# rf-transmitter.net
KiCad netlist of a schematic drawn in EAGLE
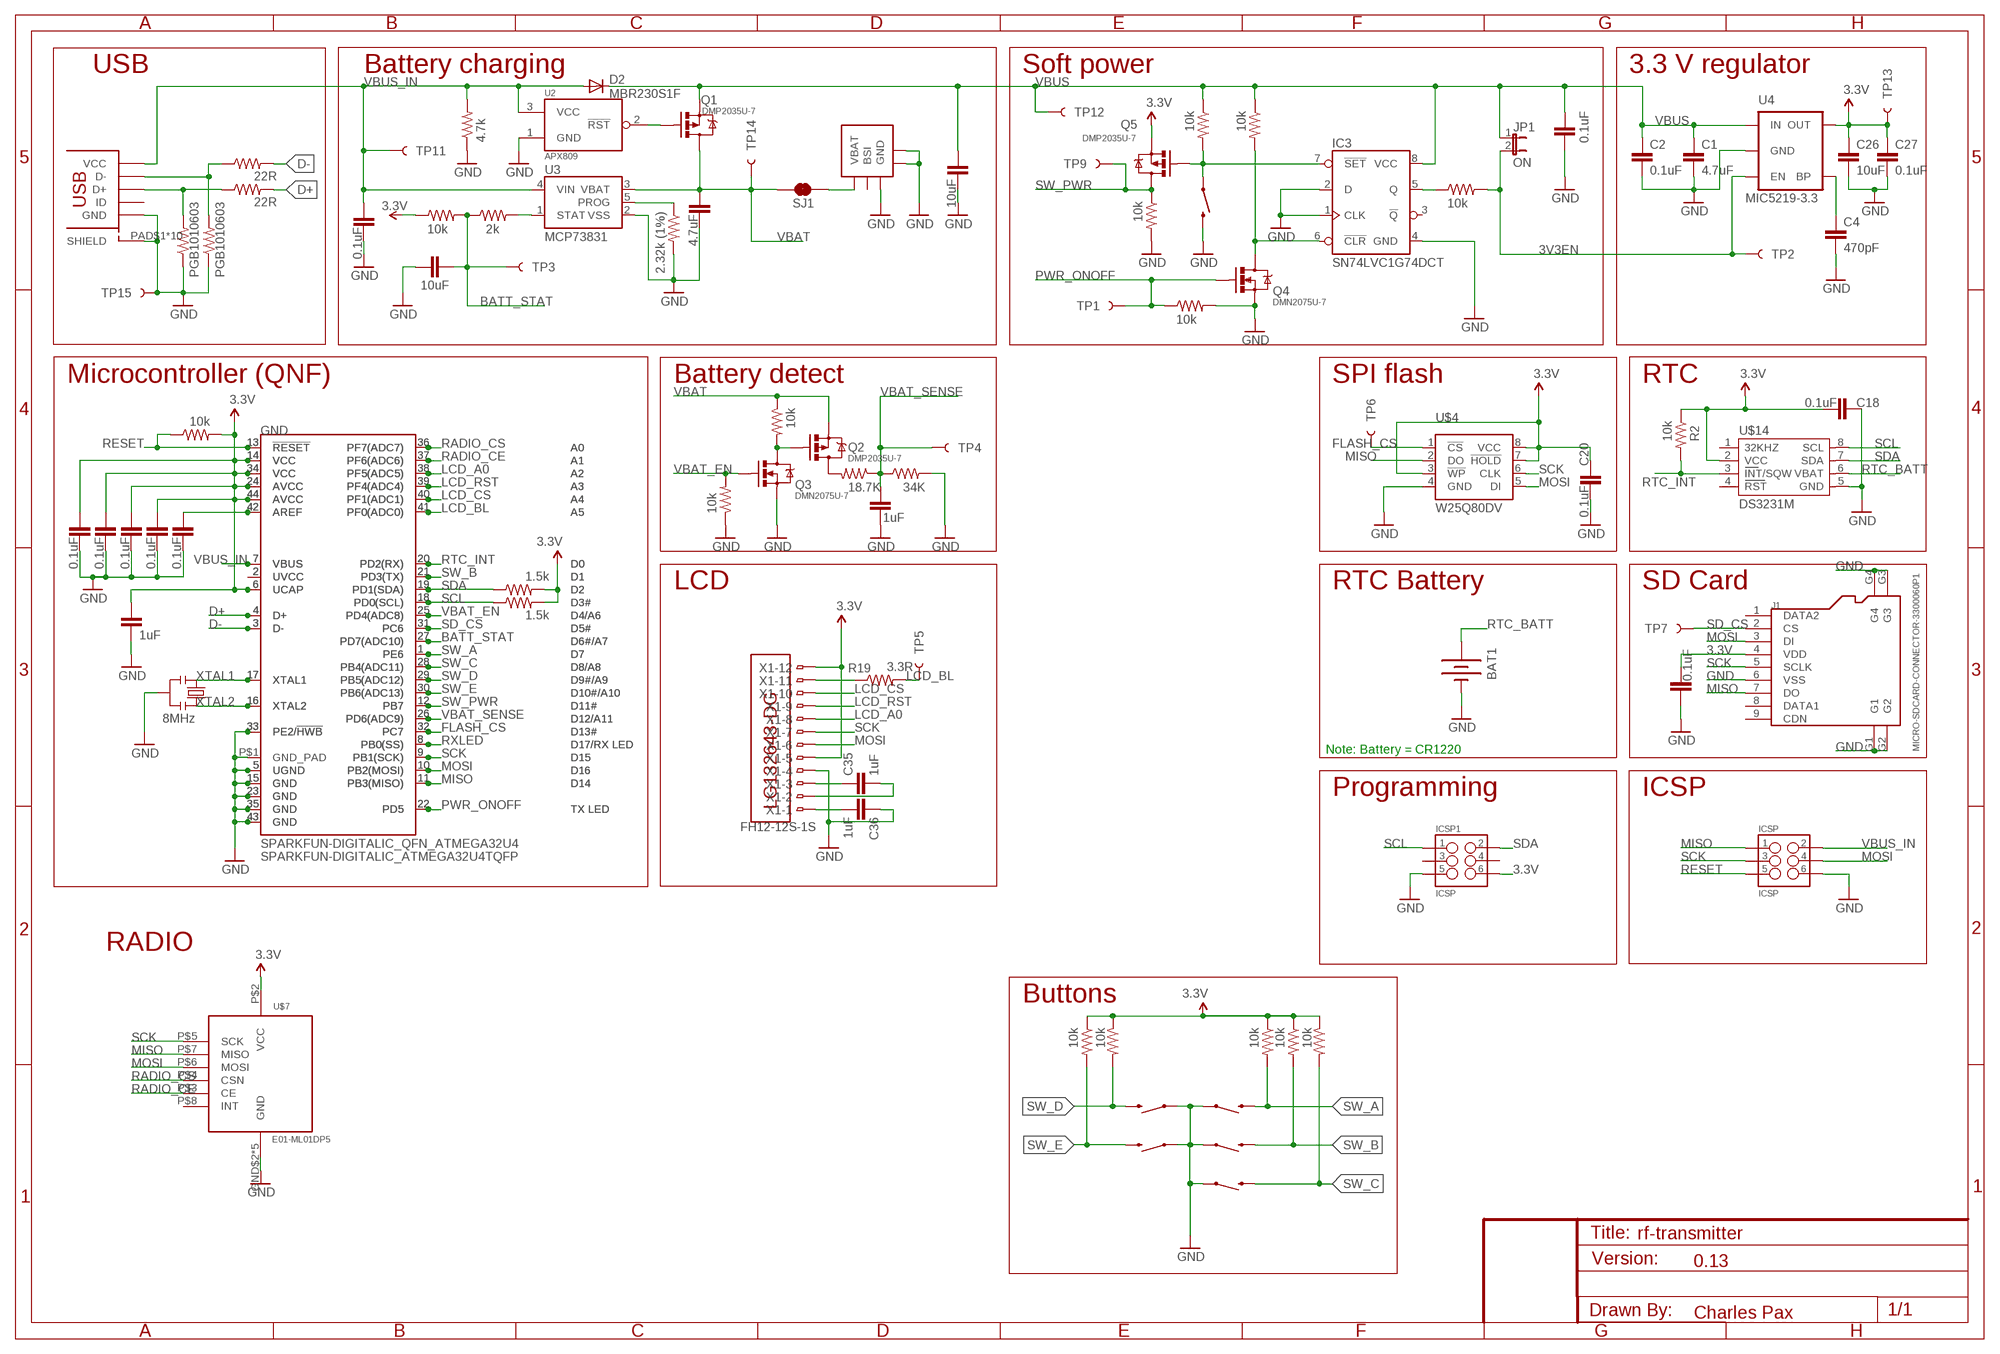
[diagram p0: schematic, sheet 1]

(export (version "E")
  (design (tool "Eeschema 10.0.6"))
  (components
    (comp (ref "BAT1")
      (value "BATTERY12MM")
      (footprint "eagle-import:BATTCON_12MM")
      (fields (field (name "MF") "Keystone Electronics") (field (name "MPN") "3000TR"))
      (libsource (lib "eagle-import") (part "BATTERY12MM"))
    )
    (comp (ref "C1")
      (value "4.7uF")
      (footprint "eagle-import:SPARKFUN-CAPACITORS_0603-CAP")
      (libsource (lib "eagle-import") (part "SPARKFUN-CAPACITORS_CAP0603-CAP"))
    )
    (comp (ref "C2")
      (value "0.1uF")
      (footprint "eagle-import:SPARKFUN-CAPACITORS_0603-CAP")
      (libsource (lib "eagle-import") (part "SPARKFUN-CAPACITORS_CAP0603-CAP"))
    )
    (comp (ref "C3")
      (value "0.1uF")
      (footprint "eagle-import:SPARKFUN-CAPACITORS_0603-CAP")
      (libsource (lib "eagle-import") (part "SPARKFUN-CAPACITORS_CAP0603-CAP"))
    )
    (comp (ref "C4")
      (value "470pF")
      (footprint "eagle-import:SPARKFUN-CAPACITORS_0603-CAP")
      (libsource (lib "eagle-import") (part "SPARKFUN-CAPACITORS_CAP0603-CAP"))
    )
    (comp (ref "C5")
      (value "0.1uF")
      (footprint "eagle-import:SPARKFUN-CAPACITORS_0603-CAP")
      (libsource (lib "eagle-import") (part "SPARKFUN-CAPACITORS_CAP0603-CAP"))
    )
    (comp (ref "C6")
      (value "0.1uF")
      (footprint "eagle-import:SPARKFUN-CAPACITORS_0603-CAP")
      (libsource (lib "eagle-import") (part "SPARKFUN-CAPACITORS_CAP0603-CAP"))
    )
    (comp (ref "C9")
      (value "4.7uF")
      (footprint "eagle-import:SPARKFUN-CAPACITORS_0603-CAP")
      (libsource (lib "eagle-import") (part "SPARKFUN-CAPACITORS_CAP0603-CAP"))
    )
    (comp (ref "C12")
      (value "10uF")
      (footprint "eagle-import:SPARKFUN-CAPACITORS_0603-CAP")
      (libsource (lib "eagle-import") (part "SPARKFUN-CAPACITORS_CAP0603-CAP"))
    )
    (comp (ref "C18")
      (value "0.1uF")
      (footprint "eagle-import:SPARKFUN-CAPACITORS_0603-CAP")
      (libsource (lib "eagle-import") (part "SPARKFUN-CAPACITORS_CAP0603-CAP"))
    )
    (comp (ref "C19")
      (value "1uF")
      (footprint "eagle-import:SPARKFUN-CAPACITORS_0603-CAP")
      (libsource (lib "eagle-import") (part "SPARKFUN-CAPACITORS_CAP0603-CAP"))
    )
    (comp (ref "C20")
      (value "0.1uF")
      (footprint "eagle-import:SPARKFUN-CAPACITORS_0603-CAP")
      (libsource (lib "eagle-import") (part "SPARKFUN-CAPACITORS_CAP0603-CAP"))
    )
    (comp (ref "C21")
      (value "0.1uF")
      (footprint "eagle-import:SPARKFUN-CAPACITORS_0603-CAP")
      (libsource (lib "eagle-import") (part "SPARKFUN-CAPACITORS_CAP0603-CAP"))
    )
    (comp (ref "C22")
      (value "10uF")
      (footprint "eagle-import:SPARKFUN-CAPACITORS_0603-CAP")
      (libsource (lib "eagle-import") (part "SPARKFUN-CAPACITORS_CAP0603-CAP"))
    )
    (comp (ref "C23")
      (value "1uF")
      (footprint "eagle-import:SPARKFUN-CAPACITORS_0603-CAP")
      (libsource (lib "eagle-import") (part "SPARKFUN-CAPACITORS_CAP0603-CAP"))
    )
    (comp (ref "C26")
      (value "10uF")
      (footprint "eagle-import:SPARKFUN-CAPACITORS_0603-CAP")
      (libsource (lib "eagle-import") (part "SPARKFUN-CAPACITORS_CAP0603-CAP"))
    )
    (comp (ref "C27")
      (value "0.1uF")
      (footprint "eagle-import:SPARKFUN-CAPACITORS_0603-CAP")
      (libsource (lib "eagle-import") (part "SPARKFUN-CAPACITORS_CAP0603-CAP"))
    )
    (comp (ref "C28")
      (value "0.1uF")
      (footprint "eagle-import:SPARKFUN-CAPACITORS_0603-CAP")
      (libsource (lib "eagle-import") (part "SPARKFUN-CAPACITORS_CAP0603-CAP"))
    )
    (comp (ref "C32")
      (value "0.1uF")
      (footprint "eagle-import:SPARKFUN-CAPACITORS_0603-CAP")
      (libsource (lib "eagle-import") (part "SPARKFUN-CAPACITORS_CAP0603-CAP"))
    )
    (comp (ref "C33")
      (value "0.1uF")
      (footprint "eagle-import:SPARKFUN-CAPACITORS_0603-CAP")
      (libsource (lib "eagle-import") (part "SPARKFUN-CAPACITORS_CAP0603-CAP"))
    )
    (comp (ref "C34")
      (value "0.1uF")
      (footprint "eagle-import:SPARKFUN-CAPACITORS_0603-CAP")
      (libsource (lib "eagle-import") (part "SPARKFUN-CAPACITORS_CAP0603-CAP"))
    )
    (comp (ref "C35")
      (value "1uF")
      (footprint "eagle-import:SPARKFUN-CAPACITORS_0603-CAP")
      (libsource (lib "eagle-import") (part "SPARKFUN-CAPACITORS_CAP0603-CAP"))
    )
    (comp (ref "C36")
      (value "1uF")
      (footprint "eagle-import:SPARKFUN-CAPACITORS_0603-CAP")
      (libsource (lib "eagle-import") (part "SPARKFUN-CAPACITORS_CAP0603-CAP"))
    )
    (comp (ref "D2")
      (value "MBR230S1F")
      (footprint "eagle-import:SOD123")
      (fields (field (name "MF") "DIODES INC") (field (name "MPN") "MBR230S1F-7"))
      (libsource (lib "eagle-import") (part "SPARKFUN-DISCRETESEMI_DIODESOD123SOD123"))
    )
    (comp (ref "GND")
      (value "SPARKFUN-DIGITALIC_QFN_ATMEGA32U4")
      (footprint "eagle-import:SPARKFUN-DIGITALIC_SPARKFUN-DIGITALIC_QFN-44")
      (fields (field (name "MF") "Atmel") (field (name "MPN") "ATMEGA32U4-MU"))
      (libsource (lib "eagle-import") (part "SPARKFUN-DIGITALIC_QFN_ATMEGA32U4"))
    )
    (comp (ref "IC3")
      (value "SN74LVC1G74DCT")
      (footprint "eagle-import:SSOP8")
      (fields (field (name "MF") "Texas Instruments") (field (name "MPN") "SN74LVC1G74DCTR "))
      (libsource (lib "eagle-import") (part "SN74LVC1G74DCT"))
    )
    (comp (ref "ICSP")
      (value "ICSP")
      (footprint "eagle-import:SPARKFUN-CONNECTORS_2X3_SMT_POSTS_PAXINSTRUMENT")
      (fields (field (name "MF") "FCI") (field (name "MPN") "95278-101A06LF"))
      (libsource (lib "eagle-import") (part "SPARKFUN-CONNECTORS_M03X2PAX"))
    )
    (comp (ref "ICSP1")
      (value "ICSP")
      (footprint "eagle-import:SPARKFUN-CONNECTORS_2X3_SMT_POSTS_PAXINSTRUMENT")
      (fields (field (name "MF") "FCI") (field (name "MPN") "95278-101A06LF"))
      (libsource (lib "eagle-import") (part "SPARKFUN-CONNECTORS_M03X2PAX"))
    )
    (comp (ref "J1")
      (value "MICRO-SDCARD-CONNECTOR-3300060P1")
      (footprint "eagle-import:9P-SMD-W-RING")
      (fields (field (name "MF") "SUNTECH") (field (name "MPN") "ST-TF-003A"))
      (libsource (lib "eagle-import") (part "MICRO-SDCARD-CONNECTOR-3300060P1"))
    )
    (comp (ref "JP1")
      (value "ON")
      (footprint "eagle-import:SJ_2S-NO")
      (libsource (lib "eagle-import") (part "JUMPER-2SMD-NO"))
    )
    (comp (ref "Q1")
      (value "DMP2035U-7")
      (footprint "eagle-import:SOT23")
      (fields (field (name "MF") "DIODES INC"))
      (libsource (lib "eagle-import") (part "MOSFET-PCHANNELSMT"))
    )
    (comp (ref "Q2")
      (value "DMP2035U-7")
      (footprint "eagle-import:SOT23")
      (fields (field (name "MF") "DIODES INC"))
      (libsource (lib "eagle-import") (part "MOSFET-PCHANNELSMT"))
    )
    (comp (ref "Q3")
      (value "DMN2075U-7")
      (footprint "eagle-import:SOT23")
      (fields (field (name "MF") "DIODES INC") (field (name "MPN") "DMN2075U-7 "))
      (libsource (lib "eagle-import") (part "MOSFET-NCHANNELSMT"))
    )
    (comp (ref "Q4")
      (value "DMN2075U-7")
      (footprint "eagle-import:SOT23")
      (fields (field (name "MF") "DIODES INC") (field (name "MPN") "DMN2075U-7 "))
      (libsource (lib "eagle-import") (part "MOSFET-NCHANNELSMT"))
    )
    (comp (ref "Q5")
      (value "DMP2035U-7")
      (footprint "eagle-import:SOT23")
      (fields (field (name "MF") "DIODES INC"))
      (libsource (lib "eagle-import") (part "MOSFET-PCHANNELSMT"))
    )
    (comp (ref "R1")
      (value "10k")
      (footprint "eagle-import:SPARKFUN-RESISTORS_0603-RES")
      (libsource (lib "eagle-import") (part "SPARKFUN-RESISTORS_RESISTOR0603-RES"))
    )
    (comp (ref "R2")
      (value "10k")
      (footprint "eagle-import:SPARKFUN-RESISTORS_0603-RES")
      (libsource (lib "eagle-import") (part "SPARKFUN-RESISTORS_RESISTOR0603-RES"))
    )
    (comp (ref "R3")
      (value "2.32k (1%)")
      (footprint "eagle-import:SPARKFUN-RESISTORS_0603-RES")
      (libsource (lib "eagle-import") (part "SPARKFUN-RESISTORS_RESISTOR0603-RES"))
    )
    (comp (ref "R4")
      (value "10k")
      (footprint "eagle-import:SPARKFUN-RESISTORS_0603-RES")
      (libsource (lib "eagle-import") (part "SPARKFUN-RESISTORS_RESISTOR0603-RES"))
    )
    (comp (ref "R5")
      (value "10k")
      (footprint "eagle-import:SPARKFUN-RESISTORS_0603-RES")
      (libsource (lib "eagle-import") (part "SPARKFUN-RESISTORS_RESISTOR0603-RES"))
    )
    (comp (ref "R6")
      (value "10k")
      (footprint "eagle-import:SPARKFUN-RESISTORS_0603-RES")
      (libsource (lib "eagle-import") (part "SPARKFUN-RESISTORS_RESISTOR0603-RES"))
    )
    (comp (ref "R7")
      (value "10k")
      (footprint "eagle-import:SPARKFUN-RESISTORS_0603-RES")
      (libsource (lib "eagle-import") (part "SPARKFUN-RESISTORS_RESISTOR0603-RES"))
    )
    (comp (ref "R8")
      (value "10k")
      (footprint "eagle-import:SPARKFUN-RESISTORS_0603-RES")
      (libsource (lib "eagle-import") (part "SPARKFUN-RESISTORS_RESISTOR0603-RES"))
    )
    (comp (ref "R9")
      (value "22R")
      (footprint "eagle-import:SPARKFUN-RESISTORS_0603-RES")
      (libsource (lib "eagle-import") (part "SPARKFUN-RESISTORS_RESISTOR0603-RES"))
    )
    (comp (ref "R10")
      (value "22R")
      (footprint "eagle-import:SPARKFUN-RESISTORS_0603-RES")
      (libsource (lib "eagle-import") (part "SPARKFUN-RESISTORS_RESISTOR0603-RES"))
    )
    (comp (ref "R11")
      (value "10k")
      (footprint "eagle-import:SPARKFUN-RESISTORS_0603-RES")
      (libsource (lib "eagle-import") (part "SPARKFUN-RESISTORS_RESISTOR0603-RES"))
    )
    (comp (ref "R12")
      (value "10k")
      (footprint "eagle-import:SPARKFUN-RESISTORS_0603-RES")
      (libsource (lib "eagle-import") (part "SPARKFUN-RESISTORS_RESISTOR0603-RES"))
    )
    (comp (ref "R13")
      (value "1.5k")
      (footprint "eagle-import:SPARKFUN-RESISTORS_0603-RES")
      (libsource (lib "eagle-import") (part "SPARKFUN-RESISTORS_RESISTOR0603-RES"))
    )
    (comp (ref "R14")
      (value "1.5k")
      (footprint "eagle-import:SPARKFUN-RESISTORS_0603-RES")
      (libsource (lib "eagle-import") (part "SPARKFUN-RESISTORS_RESISTOR0603-RES"))
    )
    (comp (ref "R15")
      (value "10k")
      (footprint "eagle-import:SPARKFUN-RESISTORS_0603-RES")
      (libsource (lib "eagle-import") (part "SPARKFUN-RESISTORS_RESISTOR0603-RES"))
    )
    (comp (ref "R16")
      (value "10k")
      (footprint "eagle-import:SPARKFUN-RESISTORS_0603-RES")
      (libsource (lib "eagle-import") (part "SPARKFUN-RESISTORS_RESISTOR0603-RES"))
    )
    (comp (ref "R17")
      (value "2k")
      (footprint "eagle-import:SPARKFUN-RESISTORS_0603-RES")
      (libsource (lib "eagle-import") (part "SPARKFUN-RESISTORS_RESISTOR0603-RES"))
    )
    (comp (ref "R18")
      (value "10k")
      (footprint "eagle-import:SPARKFUN-RESISTORS_0603-RES")
      (libsource (lib "eagle-import") (part "SPARKFUN-RESISTORS_RESISTOR0603-RES"))
    )
    (comp (ref "R19")
      (value "3.3R")
      (footprint "eagle-import:SPARKFUN-RESISTORS_0603-RES")
      (libsource (lib "eagle-import") (part "SPARKFUN-RESISTORS_RESISTOR0603-RES"))
    )
    (comp (ref "R20")
      (value "18.7K")
      (footprint "eagle-import:SPARKFUN-RESISTORS_0603-RES")
      (libsource (lib "eagle-import") (part "SPARKFUN-RESISTORS_RESISTOR0603-RES"))
    )
    (comp (ref "R21")
      (value "10k")
      (footprint "eagle-import:SPARKFUN-RESISTORS_0603-RES")
      (libsource (lib "eagle-import") (part "SPARKFUN-RESISTORS_RESISTOR0603-RES"))
    )
    (comp (ref "R22")
      (value "10k")
      (footprint "eagle-import:SPARKFUN-RESISTORS_0603-RES")
      (libsource (lib "eagle-import") (part "SPARKFUN-RESISTORS_RESISTOR0603-RES"))
    )
    (comp (ref "R23")
      (value "10k")
      (footprint "eagle-import:SPARKFUN-RESISTORS_0603-RES")
      (libsource (lib "eagle-import") (part "SPARKFUN-RESISTORS_RESISTOR0603-RES"))
    )
    (comp (ref "R24")
      (value "34K")
      (footprint "eagle-import:SPARKFUN-RESISTORS_0603-RES")
      (libsource (lib "eagle-import") (part "SPARKFUN-RESISTORS_RESISTOR0603-RES"))
    )
    (comp (ref "R25")
      (value "4.7k")
      (footprint "eagle-import:SPARKFUN-RESISTORS_0603-RES")
      (libsource (lib "eagle-import") (part "SPARKFUN-RESISTORS_RESISTOR0603-RES"))
    )
    (comp (ref "S1")
      (value "SWITCH-MOMENTARY-2SMD")
      (footprint "eagle-import:TACTILE_SWITCH_SMD")
      (fields (field (name "MF") "C&K Components") (field (name "MPN") "RS-187R05A2-DS MT RT"))
      (libsource (lib "eagle-import") (part "SWITCH-MOMENTARY-2SMD"))
    )
    (comp (ref "S2")
      (value "SWITCH-MOMENTARY-2SMD")
      (footprint "eagle-import:TACTILE_SWITCH_SMD")
      (fields (field (name "MF") "C&K Components") (field (name "MPN") "RS-187R05A2-DS MT RT"))
      (libsource (lib "eagle-import") (part "SWITCH-MOMENTARY-2SMD"))
    )
    (comp (ref "S3")
      (value "SWITCH-MOMENTARY-2SMD")
      (footprint "eagle-import:TACTILE_SWITCH_SMD")
      (fields (field (name "MF") "C&K Components") (field (name "MPN") "RS-187R05A2-DS MT RT"))
      (libsource (lib "eagle-import") (part "SWITCH-MOMENTARY-2SMD"))
    )
    (comp (ref "S4")
      (value "SWITCH-MOMENTARY-2SMD")
      (footprint "eagle-import:TACTILE_SWITCH_SMD")
      (fields (field (name "MF") "C&K Components") (field (name "MPN") "RS-187R05A2-DS MT RT"))
      (libsource (lib "eagle-import") (part "SWITCH-MOMENTARY-2SMD"))
    )
    (comp (ref "S5")
      (value "SWITCH-MOMENTARY-2SMD")
      (footprint "eagle-import:TACTILE_SWITCH_SMD")
      (fields (field (name "MF") "C&K Components") (field (name "MPN") "RS-187R05A2-DS MT RT"))
      (libsource (lib "eagle-import") (part "SWITCH-MOMENTARY-2SMD"))
    )
    (comp (ref "S6")
      (value "SWITCH-MOMENTARY-2SMD")
      (footprint "eagle-import:TACTILE_SWITCH_SMD")
      (fields (field (name "MF") "C&K Components") (field (name "MPN") "RS-187R05A2-DS MT RT"))
      (libsource (lib "eagle-import") (part "SWITCH-MOMENTARY-2SMD"))
    )
    (comp (ref "SJ1")
      (value "JUMPER-PAD-2-NC_BY_TRACE")
      (footprint "eagle-import:PAD-JUMPER-2-NC_BY_TRACE_YES_SILK")
      (libsource (lib "eagle-import") (part "JUMPER-PAD-2-NC_BY_TRACE"))
    )
    (comp (ref "TP1")
      (value "PWR_ONOFF")
      (footprint "eagle-import:TP_15TH")
      (libsource (lib "eagle-import") (part "TEST-POINTTP_15TH_THRU"))
    )
    (comp (ref "TP2")
      (value "3V3_EN")
      (footprint "eagle-import:TP_15TH")
      (libsource (lib "eagle-import") (part "TEST-POINTTP_15TH_THRU"))
    )
    (comp (ref "TP3")
      (value "BATT_STAT")
      (footprint "eagle-import:TP_15TH")
      (libsource (lib "eagle-import") (part "TEST-POINTTP_15TH_THRU"))
    )
    (comp (ref "TP4")
      (value "VBAT_SENSE")
      (footprint "eagle-import:TP_15TH")
      (libsource (lib "eagle-import") (part "TEST-POINTTP_15TH_THRU"))
    )
    (comp (ref "TP5")
      (value "LCD_BL")
      (footprint "eagle-import:TP_15TH")
      (libsource (lib "eagle-import") (part "TEST-POINTTP_15TH_THRU"))
    )
    (comp (ref "TP6")
      (value "FLASH_CS")
      (footprint "eagle-import:TP_15TH")
      (libsource (lib "eagle-import") (part "TEST-POINTTP_15TH_THRU"))
    )
    (comp (ref "TP7")
      (value "SD_CS")
      (footprint "eagle-import:TP_15TH")
      (libsource (lib "eagle-import") (part "TEST-POINTTP_15TH_THRU"))
    )
    (comp (ref "TP9")
      (value "SW_PWR")
      (footprint "eagle-import:TP_15TH")
      (libsource (lib "eagle-import") (part "TEST-POINTTP_15TH_THRU"))
    )
    (comp (ref "TP11")
      (value "VBUS_IN")
      (footprint "eagle-import:TP_15TH")
      (libsource (lib "eagle-import") (part "TEST-POINTTP_15TH_THRU"))
    )
    (comp (ref "TP12")
      (value "VBUS")
      (footprint "eagle-import:TP_15TH")
      (libsource (lib "eagle-import") (part "TEST-POINTTP_15TH_THRU"))
    )
    (comp (ref "TP13")
      (value "3.3V")
      (footprint "eagle-import:TP_15TH")
      (libsource (lib "eagle-import") (part "TEST-POINTTP_15TH_THRU"))
    )
    (comp (ref "TP14")
      (value "VBAT")
      (footprint "eagle-import:TP_15TH")
      (libsource (lib "eagle-import") (part "TEST-POINTTP_15TH_THRU"))
    )
    (comp (ref "TP15")
      (value "GND")
      (footprint "eagle-import:TP_15TH")
      (libsource (lib "eagle-import") (part "TEST-POINTTP_15TH_THRU"))
    )
    (comp (ref "U$1")
      (value "USB_MICROSMT+THRUHULE")
      (footprint "eagle-import:USB_MICRO_THRUHOLE")
      (fields (field (name "MF") "FCI") (field (name "MPN") "10118194-0001LF"))
      (libsource (lib "eagle-import") (part "USB_MICROSMT+THRUHULE"))
    )
    (comp (ref "U$2")
      (value "BL-5C-CONNECTOR")
      (footprint "eagle-import:BL-5C-CONNECTOR")
      (fields (field (name "MPN") "BC-4-3P (77H)"))
      (libsource (lib "eagle-import") (part "BL-5C-CONNECTOR"))
    )
    (comp (ref "U$3")
      (value "SPARKFUN-DIGITALIC_ATMEGA32U4TQFP")
      (footprint "eagle-import:SPARKFUN-DIGITALIC_SPARKFUN-DIGITALIC_TQFP44")
      (fields (field (name "MF") "Atmel") (field (name "MPN") "ATMEGA32U4-AU"))
      (libsource (lib "eagle-import") (part "SPARKFUN-DIGITALIC_ATMEGA32U4TQFP"))
    )
    (comp (ref "U$4")
      (value "W25Q80DV")
      (footprint "eagle-import:CHARLESPAX_SOIC8M")
      (fields (field (name "MF") "Winbond Electronics") (field (name "MPN") "W25Q80DVSSIG-ND"))
      (libsource (lib "eagle-import") (part "W25Q80BV"))
    )
    (comp (ref "U$5")
      (value "LG132643-DG")
      (footprint "eagle-import:LG132643-DG")
      (fields (field (name "MPN") "LG132643-DW"))
      (libsource (lib "eagle-import") (part "LG132643-DG"))
    )
    (comp (ref "U$7")
      (value "E01-ML01DP5")
      (footprint "eagle-import:E01-ML01DP5")
      (libsource (lib "eagle-import") (part "E01-ML01DP5"))
    )
    (comp (ref "U$14")
      (value "DS3231M")
      (footprint "eagle-import:SOIC8")
      (fields (field (name "MF") "Maxim Integrated") (field (name "MPN") "DS3231MZ+"))
      (libsource (lib "eagle-import") (part "DS3231M"))
    )
    (comp (ref "U2")
      (value "APX809")
      (footprint "eagle-import:SOT23")
      (fields (field (name "MF") "DIODES INC") (field (name "MPN") "APX809-44SAG-7"))
      (libsource (lib "eagle-import") (part "APX809"))
    )
    (comp (ref "U3")
      (value "MCP73831")
      (footprint "eagle-import:SOT23-5")
      (fields (field (name "MF") "Microchip Technology") (field (name "MPN") "MCP73832T-2DCI/OT"))
      (libsource (lib "eagle-import") (part "MCP73831"))
    )
    (comp (ref "U4")
      (value "MIC5219-3.3V")
      (footprint "eagle-import:SOT23-5")
      (fields (field (name "MF") "Micrel") (field (name "MPN") "MIC5219-3.3YM5 TR"))
      (libsource (lib "eagle-import") (part "V_REG_LDOSMD"))
    )
    (comp (ref "X1")
      (value "FH12-12S-1S")
      (footprint "eagle-import:FH12-12S-1SH")
      (fields (field (name "MF") "Hirose Connector") (field (name "MPN") "FH12-12S-1SH(55)"))
      (libsource (lib "eagle-import") (part "FH12-12S-1S"))
    )
    (comp (ref "Y1")
      (value "RESONATORSMD")
      (footprint "eagle-import:RESONATOR-SMD")
      (fields (field (name "MF") "Murata Electronics") (field (name "MPN") "CSTCE8M00G52-R0"))
      (libsource (lib "eagle-import") (part "RESONATORSMD"))
    )
    (comp (ref "Z1")
      (value "PGB1010603")
      (footprint "eagle-import:SPARKFUN-RESISTORS_0603-RES")
      (fields (field (name "MF") "Littelfuse") (field (name "MPN") "PGB1010603NRHF"))
      (libsource (lib "eagle-import") (part "SPARKFUN-RESISTORS_RESISTOR0603-RES"))
    )
    (comp (ref "Z2")
      (value "PGB1010603")
      (footprint "eagle-import:SPARKFUN-RESISTORS_0603-RES")
      (fields (field (name "MF") "Littelfuse") (field (name "MPN") "PGB1010603NRHF"))
      (libsource (lib "eagle-import") (part "SPARKFUN-RESISTORS_RESISTOR0603-RES"))
    )
  )
  (nets
    (net (code "1") (name "/3V3EN") (class "Default")
      (node (ref "JP1") (pin "2") (pinfunction "2_2") (pintype "passive"))
      (node (ref "R21") (pin "2") (pinfunction "2_2") (pintype "passive"))
      (node (ref "TP2") (pin "P$1") (pinfunction "1_P$1") (pintype "bidirectional"))
      (node (ref "U4") (pin "3") (pinfunction "EN_3") (pintype "input"))
    )
    (net (code "2") (name "/BATT_STAT") (class "Default")
      (node (ref "C22") (pin "1") (pinfunction "1_1") (pintype "passive"))
      (node (ref "GND") (pin "27") (pinfunction "PD7(ADC10)_27") (pintype "bidirectional"))
      (node (ref "R1") (pin "2") (pinfunction "2_2") (pintype "passive"))
      (node (ref "R17") (pin "1") (pinfunction "1_1") (pintype "passive"))
      (node (ref "TP3") (pin "P$1") (pinfunction "1_P$1") (pintype "bidirectional"))
      (node (ref "U$3") (pin "27") (pinfunction "PD7(ADC10)_27") (pintype "bidirectional"))
    )
    (net (code "3") (name "/FLASH_CS") (class "Default")
      (node (ref "GND") (pin "32") (pinfunction "PC7_32") (pintype "bidirectional"))
      (node (ref "TP6") (pin "P$1") (pinfunction "1_P$1") (pintype "bidirectional"))
      (node (ref "U$3") (pin "32") (pinfunction "PC7_32") (pintype "bidirectional"))
      (node (ref "U$4") (pin "1") (pinfunction "~{CS}_1") (pintype "bidirectional"))
    )
    (net (code "4") (name "/LCD_A0") (class "Default")
      (node (ref "GND") (pin "38") (pinfunction "PF5(ADC5)_38") (pintype "bidirectional"))
      (node (ref "U$3") (pin "38") (pinfunction "PF5(ADC5)_38") (pintype "bidirectional"))
      (node (ref "X1") (pin "8") (pinfunction "1_8") (pintype "passive"))
    )
    (net (code "5") (name "/LCD_BL") (class "Default")
      (node (ref "GND") (pin "41") (pinfunction "PF0(ADC0)_41") (pintype "bidirectional"))
      (node (ref "R19") (pin "2") (pinfunction "2_2") (pintype "passive"))
      (node (ref "TP5") (pin "P$1") (pinfunction "1_P$1") (pintype "bidirectional"))
      (node (ref "U$3") (pin "41") (pinfunction "PF0(ADC0)_41") (pintype "bidirectional"))
    )
    (net (code "6") (name "/LCD_CS") (class "Default")
      (node (ref "GND") (pin "40") (pinfunction "PF1(ADC1)_40") (pintype "bidirectional"))
      (node (ref "U$3") (pin "40") (pinfunction "PF1(ADC1)_40") (pintype "bidirectional"))
      (node (ref "X1") (pin "10") (pinfunction "1_10") (pintype "passive"))
    )
    (net (code "7") (name "/LCD_RST") (class "Default")
      (node (ref "GND") (pin "39") (pinfunction "PF4(ADC4)_39") (pintype "bidirectional"))
      (node (ref "U$3") (pin "39") (pinfunction "PF4(ADC4)_39") (pintype "bidirectional"))
      (node (ref "X1") (pin "9") (pinfunction "1_9") (pintype "passive"))
    )
    (net (code "8") (name "/MISO") (class "Default")
      (node (ref "GND") (pin "11") (pinfunction "PB3(MISO)_11") (pintype "bidirectional"))
      (node (ref "ICSP") (pin "1") (pinfunction "1_1") (pintype "bidirectional"))
      (node (ref "J1") (pin "7") (pinfunction "DO_7") (pintype "bidirectional"))
      (node (ref "U$3") (pin "11") (pinfunction "PB3(MISO)_11") (pintype "bidirectional"))
      (node (ref "U$4") (pin "2") (pinfunction "DO_2") (pintype "bidirectional"))
      (node (ref "U$7") (pin "P$7") (pinfunction "MISO_P$7") (pintype "input"))
    )
    (net (code "9") (name "/MOSI") (class "Default")
      (node (ref "GND") (pin "10") (pinfunction "PB2(MOSI)_10") (pintype "bidirectional"))
      (node (ref "ICSP") (pin "4") (pinfunction "4_4") (pintype "bidirectional"))
      (node (ref "J1") (pin "3") (pinfunction "DI_3") (pintype "bidirectional"))
      (node (ref "U$3") (pin "10") (pinfunction "PB2(MOSI)_10") (pintype "bidirectional"))
      (node (ref "U$4") (pin "5") (pinfunction "DI_5") (pintype "bidirectional"))
      (node (ref "U$7") (pin "P$6") (pinfunction "MOSI_P$6") (pintype "input"))
      (node (ref "X1") (pin "6") (pinfunction "1_6") (pintype "passive"))
    )
    (net (code "10") (name "/PWR_ONOFF") (class "Default")
      (node (ref "GND") (pin "22") (pinfunction "PD5_22") (pintype "bidirectional"))
      (node (ref "Q4") (pin "1") (pinfunction "G_1") (pintype "passive"))
      (node (ref "R22") (pin "1") (pinfunction "1_1") (pintype "passive"))
      (node (ref "TP1") (pin "P$1") (pinfunction "1_P$1") (pintype "bidirectional"))
      (node (ref "U$3") (pin "22") (pinfunction "PD5_22") (pintype "bidirectional"))
    )
    (net (code "11") (name "/RADIO_CE") (class "Default")
      (node (ref "GND") (pin "37") (pinfunction "PF6(ADC6)_37") (pintype "bidirectional"))
      (node (ref "U$3") (pin "37") (pinfunction "PF6(ADC6)_37") (pintype "bidirectional"))
      (node (ref "U$7") (pin "P$3") (pinfunction "CE_P$3") (pintype "input"))
    )
    (net (code "12") (name "/RADIO_CS") (class "Default")
      (node (ref "GND") (pin "36") (pinfunction "PF7(ADC7)_36") (pintype "bidirectional"))
      (node (ref "U$3") (pin "36") (pinfunction "PF7(ADC7)_36") (pintype "bidirectional"))
      (node (ref "U$7") (pin "P$4") (pinfunction "CSN_P$4") (pintype "input"))
    )
    (net (code "13") (name "/RESET") (class "Default")
      (node (ref "GND") (pin "13") (pinfunction "~{RESET}_13") (pintype "bidirectional"))
      (node (ref "ICSP") (pin "5") (pinfunction "5_5") (pintype "bidirectional"))
      (node (ref "R4") (pin "1") (pinfunction "1_1") (pintype "passive"))
      (node (ref "U$3") (pin "13") (pinfunction "~{RESET}_13") (pintype "bidirectional"))
    )
    (net (code "14") (name "/RTC_BATT") (class "Default")
      (node (ref "BAT1") (pin "PWR@1") (pinfunction "+_PWR@1") (pintype "power_in"))
      (node (ref "U$14") (pin "6") (pinfunction "VBAT_6") (pintype "input"))
    )
    (net (code "15") (name "/RTC_INT") (class "Default")
      (node (ref "GND") (pin "20") (pinfunction "PD2(RX)_20") (pintype "bidirectional"))
      (node (ref "R2") (pin "2") (pinfunction "2_2") (pintype "passive"))
      (node (ref "U$14") (pin "3") (pinfunction "INT/SQW_3") (pintype "output"))
      (node (ref "U$3") (pin "20") (pinfunction "PD2(RX)_20") (pintype "bidirectional"))
    )
    (net (code "16") (name "/RXLED") (class "Default")
      (node (ref "GND") (pin "8") (pinfunction "PB0(SS)_8") (pintype "bidirectional"))
      (node (ref "U$3") (pin "8") (pinfunction "PB0(SS)_8") (pintype "bidirectional"))
    )
    (net (code "17") (name "/SCK") (class "Default")
      (node (ref "GND") (pin "9") (pinfunction "PB1(SCK)_9") (pintype "bidirectional"))
      (node (ref "ICSP") (pin "3") (pinfunction "3_3") (pintype "bidirectional"))
      (node (ref "J1") (pin "5") (pinfunction "SCLK_5") (pintype "bidirectional"))
      (node (ref "U$3") (pin "9") (pinfunction "PB1(SCK)_9") (pintype "bidirectional"))
      (node (ref "U$4") (pin "6") (pinfunction "CLK_6") (pintype "bidirectional"))
      (node (ref "U$7") (pin "P$5") (pinfunction "SCK_P$5") (pintype "input"))
      (node (ref "X1") (pin "7") (pinfunction "1_7") (pintype "passive"))
    )
    (net (code "18") (name "/SCL") (class "Default")
      (node (ref "GND") (pin "18") (pinfunction "PD0(SCL)_18") (pintype "bidirectional"))
      (node (ref "ICSP1") (pin "1") (pinfunction "1_1") (pintype "bidirectional"))
      (node (ref "R14") (pin "1") (pinfunction "1_1") (pintype "passive"))
      (node (ref "U$14") (pin "8") (pinfunction "SCL_8") (pintype "input"))
      (node (ref "U$3") (pin "18") (pinfunction "PD0(SCL)_18") (pintype "bidirectional"))
    )
    (net (code "19") (name "/SDA") (class "Default")
      (node (ref "GND") (pin "19") (pinfunction "PD1(SDA)_19") (pintype "bidirectional"))
      (node (ref "ICSP1") (pin "2") (pinfunction "2_2") (pintype "bidirectional"))
      (node (ref "R13") (pin "1") (pinfunction "1_1") (pintype "passive"))
      (node (ref "U$14") (pin "7") (pinfunction "SDA_7") (pintype "bidirectional"))
      (node (ref "U$3") (pin "19") (pinfunction "PD1(SDA)_19") (pintype "bidirectional"))
    )
    (net (code "20") (name "/SD_CS") (class "Default")
      (node (ref "GND") (pin "31") (pinfunction "PC6_31") (pintype "bidirectional"))
      (node (ref "J1") (pin "2") (pinfunction "CS_2") (pintype "bidirectional"))
      (node (ref "TP7") (pin "P$1") (pinfunction "1_P$1") (pintype "bidirectional"))
      (node (ref "U$3") (pin "31") (pinfunction "PC6_31") (pintype "bidirectional"))
    )
    (net (code "21") (name "/SW_PWR") (class "Default")
      (node (ref "GND") (pin "12") (pinfunction "PB7_12") (pintype "bidirectional"))
      (node (ref "Q5") (pin "3") (pinfunction "D_3") (pintype "passive"))
      (node (ref "R18") (pin "1") (pinfunction "1_1") (pintype "passive"))
      (node (ref "TP9") (pin "P$1") (pinfunction "1_P$1") (pintype "bidirectional"))
      (node (ref "U$3") (pin "12") (pinfunction "PB7_12") (pintype "bidirectional"))
    )
    (net (code "22") (name "/VBAT") (class "Default")
      (node (ref "C9") (pin "1") (pinfunction "1_1") (pintype "passive"))
      (node (ref "Q1") (pin "3") (pinfunction "D_3") (pintype "passive"))
      (node (ref "Q2") (pin "2") (pinfunction "S_2") (pintype "passive"))
      (node (ref "R5") (pin "1") (pinfunction "1_1") (pintype "passive"))
      (node (ref "SJ1") (pin "1") (pinfunction "1_1") (pintype "passive"))
      (node (ref "TP14") (pin "P$1") (pinfunction "1_P$1") (pintype "bidirectional"))
      (node (ref "U3") (pin "3") (pinfunction "VBAT_3") (pintype "power_in"))
    )
    (net (code "23") (name "/VBAT_EN") (class "Default")
      (node (ref "GND") (pin "25") (pinfunction "PD4(ADC8)_25") (pintype "bidirectional"))
      (node (ref "Q3") (pin "1") (pinfunction "G_1") (pintype "passive"))
      (node (ref "R23") (pin "2") (pinfunction "2_2") (pintype "passive"))
      (node (ref "U$3") (pin "25") (pinfunction "PD4(ADC8)_25") (pintype "bidirectional"))
    )
    (net (code "24") (name "/VBAT_SENSE") (class "Default")
      (node (ref "C23") (pin "1") (pinfunction "1_1") (pintype "passive"))
      (node (ref "GND") (pin "26") (pinfunction "PD6(ADC9)_26") (pintype "bidirectional"))
      (node (ref "R20") (pin "1") (pinfunction "1_1") (pintype "passive"))
      (node (ref "R24") (pin "1") (pinfunction "1_1") (pintype "passive"))
      (node (ref "TP4") (pin "P$1") (pinfunction "1_P$1") (pintype "bidirectional"))
      (node (ref "U$3") (pin "26") (pinfunction "PD6(ADC9)_26") (pintype "bidirectional"))
    )
    (net (code "25") (name "/VBUS") (class "Default")
      (node (ref "C1") (pin "1") (pinfunction "1_1") (pintype "passive"))
      (node (ref "C12") (pin "1") (pinfunction "1_1") (pintype "passive"))
      (node (ref "C2") (pin "1") (pinfunction "1_1") (pintype "passive"))
      (node (ref "C28") (pin "1") (pinfunction "1_1") (pintype "passive"))
      (node (ref "D2") (pin "C") (pinfunction "C_C") (pintype "passive"))
      (node (ref "IC3") (pin "8") (pinfunction "VCC_8") (pintype "power_in"))
      (node (ref "JP1") (pin "1") (pinfunction "1_1") (pintype "passive"))
      (node (ref "Q1") (pin "2") (pinfunction "S_2") (pintype "passive"))
      (node (ref "R6") (pin "1") (pinfunction "1_1") (pintype "passive"))
      (node (ref "R7") (pin "1") (pinfunction "1_1") (pintype "passive"))
      (node (ref "TP12") (pin "P$1") (pinfunction "1_P$1") (pintype "bidirectional"))
      (node (ref "U4") (pin "1") (pinfunction "IN_1") (pintype "input"))
    )
    (net (code "26") (name "/VBUS_IN") (class "Default")
      (node (ref "C6") (pin "1") (pinfunction "1_1") (pintype "passive"))
      (node (ref "D2") (pin "A") (pinfunction "A_A") (pintype "passive"))
      (node (ref "GND") (pin "7") (pinfunction "VBUS_7") (pintype "bidirectional"))
      (node (ref "ICSP") (pin "2") (pinfunction "2_2") (pintype "bidirectional"))
      (node (ref "R25") (pin "2") (pinfunction "2_2") (pintype "passive"))
      (node (ref "TP11") (pin "P$1") (pinfunction "1_P$1") (pintype "bidirectional"))
      (node (ref "U$1") (pin "PIN$1") (pinfunction "VCC_PIN$1") (pintype "bidirectional"))
      (node (ref "U$3") (pin "7") (pinfunction "VBUS_7") (pintype "bidirectional"))
      (node (ref "U2") (pin "3") (pinfunction "VCC_3") (pintype "power_in"))
      (node (ref "U3") (pin "4") (pinfunction "VIN_4") (pintype "power_in"))
    )
    (net (code "27") (name "/XTAL1") (class "Default")
      (node (ref "GND") (pin "17") (pinfunction "XTAL1_17") (pintype "bidirectional"))
      (node (ref "U$3") (pin "17") (pinfunction "XTAL1_17") (pintype "bidirectional"))
      (node (ref "Y1") (pin "1") (pinfunction "1_1") (pintype "passive"))
    )
    (net (code "28") (name "/XTAL2") (class "Default")
      (node (ref "GND") (pin "16") (pinfunction "XTAL2_16") (pintype "bidirectional"))
      (node (ref "U$3") (pin "16") (pinfunction "XTAL2_16") (pintype "bidirectional"))
      (node (ref "Y1") (pin "3") (pinfunction "3_3") (pintype "passive"))
    )
    (net (code "29") (name "3.3V") (class "Default")
      (node (ref "C18") (pin "1") (pinfunction "1_1") (pintype "passive"))
      (node (ref "C19") (pin "1") (pinfunction "1_1") (pintype "passive"))
      (node (ref "C20") (pin "2") (pinfunction "2_2") (pintype "passive"))
      (node (ref "C21") (pin "2") (pinfunction "2_2") (pintype "passive"))
      (node (ref "C26") (pin "1") (pinfunction "1_1") (pintype "passive"))
      (node (ref "C27") (pin "1") (pinfunction "1_1") (pintype "passive"))
      (node (ref "C32") (pin "1") (pinfunction "1_1") (pintype "passive"))
      (node (ref "C33") (pin "1") (pinfunction "1_1") (pintype "passive"))
      (node (ref "C34") (pin "1") (pinfunction "1_1") (pintype "passive"))
      (node (ref "C5") (pin "1") (pinfunction "1_1") (pintype "passive"))
      (node (ref "GND") (pin "14") (pinfunction "VCC_14") (pintype "bidirectional"))
      (node (ref "GND") (pin "24") (pinfunction "AVCC_24") (pintype "bidirectional"))
      (node (ref "GND") (pin "34") (pinfunction "VCC_34") (pintype "bidirectional"))
      (node (ref "GND") (pin "44") (pinfunction "AVCC_44") (pintype "bidirectional"))
      (node (ref "GND") (pin "6") (pinfunction "UCAP_6") (pintype "bidirectional"))
      (node (ref "ICSP1") (pin "6") (pinfunction "6_6") (pintype "bidirectional"))
      (node (ref "J1") (pin "4") (pinfunction "VDD_4") (pintype "bidirectional"))
      (node (ref "Q5") (pin "2") (pinfunction "S_2") (pintype "passive"))
      (node (ref "R1") (pin "1") (pinfunction "1_1") (pintype "passive"))
      (node (ref "R11") (pin "1") (pinfunction "1_1") (pintype "passive"))
      (node (ref "R12") (pin "1") (pinfunction "1_1") (pintype "passive"))
      (node (ref "R13") (pin "2") (pinfunction "2_2") (pintype "passive"))
      (node (ref "R14") (pin "2") (pinfunction "2_2") (pintype "passive"))
      (node (ref "R15") (pin "1") (pinfunction "1_1") (pintype "passive"))
      (node (ref "R16") (pin "1") (pinfunction "1_1") (pintype "passive"))
      (node (ref "R2") (pin "1") (pinfunction "1_1") (pintype "passive"))
      (node (ref "R4") (pin "2") (pinfunction "2_2") (pintype "passive"))
      (node (ref "R8") (pin "1") (pinfunction "1_1") (pintype "passive"))
      (node (ref "TP13") (pin "P$1") (pinfunction "1_P$1") (pintype "bidirectional"))
      (node (ref "U$14") (pin "2") (pinfunction "VCC_2") (pintype "power_in"))
      (node (ref "U$3") (pin "14") (pinfunction "VCC_14") (pintype "bidirectional"))
      (node (ref "U$3") (pin "24") (pinfunction "AVCC_24") (pintype "bidirectional"))
      (node (ref "U$3") (pin "34") (pinfunction "VCC_34") (pintype "bidirectional"))
      (node (ref "U$3") (pin "44") (pinfunction "AVCC_44") (pintype "bidirectional"))
      (node (ref "U$3") (pin "6") (pinfunction "UCAP_6") (pintype "bidirectional"))
      (node (ref "U$4") (pin "3") (pinfunction "~{WP}_3") (pintype "bidirectional"))
      (node (ref "U$4") (pin "7") (pinfunction "~{HOLD}_7") (pintype "bidirectional"))
      (node (ref "U$4") (pin "8") (pinfunction "VCC_8") (pintype "bidirectional"))
      (node (ref "U$7") (pin "P$2") (pinfunction "VCC_P$2") (pintype "power_in"))
      (node (ref "U4") (pin "5") (pinfunction "OUT_5") (pintype "passive"))
      (node (ref "X1") (pin "12") (pinfunction "1_12") (pintype "passive"))
      (node (ref "X1") (pin "5") (pinfunction "1_5") (pintype "passive"))
    )
    (net (code "30") (name "D+") (class "Default")
      (node (ref "GND") (pin "4") (pinfunction "D+_4") (pintype "bidirectional"))
      (node (ref "R9") (pin "2") (pinfunction "2_2") (pintype "passive"))
      (node (ref "U$3") (pin "4") (pinfunction "D+_4") (pintype "bidirectional"))
    )
    (net (code "31") (name "D-") (class "Default")
      (node (ref "GND") (pin "3") (pinfunction "D-_3") (pintype "bidirectional"))
      (node (ref "R10") (pin "2") (pinfunction "2_2") (pintype "passive"))
      (node (ref "U$3") (pin "3") (pinfunction "D-_3") (pintype "bidirectional"))
    )
    (net (code "32") (name "GND") (class "Default")
      (node (ref "BAT1") (pin "GND") (pinfunction "-_GND") (pintype "power_in"))
      (node (ref "C1") (pin "2") (pinfunction "2_2") (pintype "passive"))
      (node (ref "C12") (pin "2") (pinfunction "2_2") (pintype "passive"))
      (node (ref "C18") (pin "2") (pinfunction "2_2") (pintype "passive"))
      (node (ref "C19") (pin "2") (pinfunction "2_2") (pintype "passive"))
      (node (ref "C2") (pin "2") (pinfunction "2_2") (pintype "passive"))
      (node (ref "C20") (pin "1") (pinfunction "1_1") (pintype "passive"))
      (node (ref "C21") (pin "1") (pinfunction "1_1") (pintype "passive"))
      (node (ref "C22") (pin "2") (pinfunction "2_2") (pintype "passive"))
      (node (ref "C23") (pin "2") (pinfunction "2_2") (pintype "passive"))
      (node (ref "C26") (pin "2") (pinfunction "2_2") (pintype "passive"))
      (node (ref "C27") (pin "2") (pinfunction "2_2") (pintype "passive"))
      (node (ref "C28") (pin "2") (pinfunction "2_2") (pintype "passive"))
      (node (ref "C3") (pin "2") (pinfunction "2_2") (pintype "passive"))
      (node (ref "C32") (pin "2") (pinfunction "2_2") (pintype "passive"))
      (node (ref "C33") (pin "2") (pinfunction "2_2") (pintype "passive"))
      (node (ref "C34") (pin "2") (pinfunction "2_2") (pintype "passive"))
      (node (ref "C36") (pin "1") (pinfunction "1_1") (pintype "passive"))
      (node (ref "C4") (pin "2") (pinfunction "2_2") (pintype "passive"))
      (node (ref "C5") (pin "2") (pinfunction "2_2") (pintype "passive"))
      (node (ref "C6") (pin "2") (pinfunction "2_2") (pintype "passive"))
      (node (ref "C9") (pin "2") (pinfunction "2_2") (pintype "passive"))
      (node (ref "GND") (pin "15") (pinfunction "GND_15") (pintype "bidirectional"))
      (node (ref "GND") (pin "23") (pinfunction "GND_23") (pintype "bidirectional"))
      (node (ref "GND") (pin "33") (pinfunction "PE2/~{HWB}_33") (pintype "bidirectional"))
      (node (ref "GND") (pin "35") (pinfunction "GND_35") (pintype "bidirectional"))
      (node (ref "GND") (pin "43") (pinfunction "GND_43") (pintype "bidirectional"))
      (node (ref "GND") (pin "5") (pinfunction "UGND_5") (pintype "bidirectional"))
      (node (ref "GND") (pin "P$1") (pinfunction "GND_PAD_P$1") (pintype "bidirectional"))
      (node (ref "IC3") (pin "1") (pinfunction "CLK_1") (pintype "input"))
      (node (ref "IC3") (pin "2") (pinfunction "D_2") (pintype "input"))
      (node (ref "IC3") (pin "4") (pinfunction "GND_4") (pintype "power_in"))
      (node (ref "ICSP") (pin "6") (pinfunction "6_6") (pintype "bidirectional"))
      (node (ref "ICSP1") (pin "5") (pinfunction "5_5") (pintype "bidirectional"))
      (node (ref "J1") (pin "6") (pinfunction "VSS_6") (pintype "bidirectional"))
      (node (ref "J1") (pin "G1") (pinfunction "G1_G1") (pintype "bidirectional"))
      (node (ref "J1") (pin "G2") (pinfunction "G2_G2") (pintype "bidirectional"))
      (node (ref "J1") (pin "G3") (pinfunction "G3_G3") (pintype "bidirectional"))
      (node (ref "J1") (pin "G4") (pinfunction "G4_G4") (pintype "bidirectional"))
      (node (ref "Q3") (pin "2") (pinfunction "S_2") (pintype "passive"))
      (node (ref "Q4") (pin "2") (pinfunction "S_2") (pintype "passive"))
      (node (ref "R18") (pin "2") (pinfunction "2_2") (pintype "passive"))
      (node (ref "R22") (pin "2") (pinfunction "2_2") (pintype "passive"))
      (node (ref "R23") (pin "1") (pinfunction "1_1") (pintype "passive"))
      (node (ref "R24") (pin "2") (pinfunction "2_2") (pintype "passive"))
      (node (ref "R25") (pin "1") (pinfunction "1_1") (pintype "passive"))
      (node (ref "R3") (pin "2") (pinfunction "2_2") (pintype "passive"))
      (node (ref "S1") (pin "1") (pinfunction "1_1") (pintype "passive"))
      (node (ref "S2") (pin "1") (pinfunction "1_1") (pintype "passive"))
      (node (ref "S3") (pin "1") (pinfunction "1_1") (pintype "passive"))
      (node (ref "S4") (pin "1") (pinfunction "1_1") (pintype "passive"))
      (node (ref "S5") (pin "1") (pinfunction "1_1") (pintype "passive"))
      (node (ref "S6") (pin "3") (pinfunction "2_3") (pintype "passive"))
      (node (ref "TP15") (pin "P$1") (pinfunction "1_P$1") (pintype "bidirectional"))
      (node (ref "U$1") (pin "PAD$1") (pinfunction "SHIELD_PAD$1") (pintype "bidirectional"))
      (node (ref "U$1") (pin "PAD$10") (pinfunction "SHIELD_PAD$10") (pintype "bidirectional"))
      (node (ref "U$1") (pin "PAD$2") (pinfunction "SHIELD_PAD$2") (pintype "bidirectional"))
      (node (ref "U$1") (pin "PAD$3") (pinfunction "SHIELD_PAD$3") (pintype "bidirectional"))
      (node (ref "U$1") (pin "PAD$4") (pinfunction "SHIELD_PAD$4") (pintype "bidirectional"))
      (node (ref "U$1") (pin "PAD$5") (pinfunction "SHIELD_PAD$5") (pintype "bidirectional"))
      (node (ref "U$1") (pin "PAD$6") (pinfunction "SHIELD_PAD$6") (pintype "bidirectional"))
      (node (ref "U$1") (pin "PAD$7") (pinfunction "SHIELD_PAD$7") (pintype "bidirectional"))
      (node (ref "U$1") (pin "PAD$8") (pinfunction "SHIELD_PAD$8") (pintype "bidirectional"))
      (node (ref "U$1") (pin "PAD$9") (pinfunction "SHIELD_PAD$9") (pintype "bidirectional"))
      (node (ref "U$1") (pin "PIN$5") (pinfunction "GND_PIN$5") (pintype "bidirectional"))
      (node (ref "U$14") (pin "5") (pinfunction "GND_5") (pintype "power_in"))
      (node (ref "U$2") (pin "P$3") (pinfunction "GND_P$3") (pintype "bidirectional"))
      (node (ref "U$2") (pin "P$4") (pinfunction "P$4_P$4") (pintype "bidirectional"))
      (node (ref "U$2") (pin "P$5") (pinfunction "P$5_P$5") (pintype "bidirectional"))
      (node (ref "U$3") (pin "15") (pinfunction "GND_15") (pintype "bidirectional"))
      (node (ref "U$3") (pin "23") (pinfunction "GND_23") (pintype "bidirectional"))
      (node (ref "U$3") (pin "33") (pinfunction "PE2/~{HWB}_33") (pintype "bidirectional"))
      (node (ref "U$3") (pin "35") (pinfunction "GND_35") (pintype "bidirectional"))
      (node (ref "U$3") (pin "43") (pinfunction "GND_43") (pintype "bidirectional"))
      (node (ref "U$3") (pin "5") (pinfunction "UGND_5") (pintype "bidirectional"))
      (node (ref "U$4") (pin "4") (pinfunction "GND_4") (pintype "bidirectional"))
      (node (ref "U$7") (pin "GND$2") (pinfunction "GND_GND$2") (pintype "power_in"))
      (node (ref "U$7") (pin "GND$3") (pinfunction "GND_GND$3") (pintype "power_in"))
      (node (ref "U$7") (pin "GND$4") (pinfunction "GND_GND$4") (pintype "power_in"))
      (node (ref "U$7") (pin "GND$5") (pinfunction "GND_GND$5") (pintype "power_in"))
      (node (ref "U$7") (pin "P$1") (pinfunction "GND_P$1") (pintype "power_in"))
      (node (ref "U2") (pin "1") (pinfunction "GND_1") (pintype "power_in"))
      (node (ref "U3") (pin "2") (pinfunction "VSS_2") (pintype "power_in"))
      (node (ref "U4") (pin "2") (pinfunction "GND_2") (pintype "input"))
      (node (ref "X1") (pin "4") (pinfunction "1_4") (pintype "passive"))
      (node (ref "Y1") (pin "2") (pinfunction "2_2") (pintype "passive"))
      (node (ref "Z1") (pin "1") (pinfunction "1_1") (pintype "passive"))
      (node (ref "Z2") (pin "1") (pinfunction "1_1") (pintype "passive"))
    )
    (net (code "33") (name "Net-(C36-Pad2)") (class "Default")
      (node (ref "C36") (pin "2") (pinfunction "2_2") (pintype "passive"))
      (node (ref "X1") (pin "1") (pinfunction "1_1") (pintype "passive"))
    )
    (net (code "34") (name "Net-(GND-AREF)") (class "Default")
      (node (ref "C3") (pin "1") (pinfunction "1_1") (pintype "passive"))
      (node (ref "GND") (pin "42") (pinfunction "AREF_42") (pintype "bidirectional"))
      (node (ref "U$3") (pin "42") (pinfunction "AREF_42") (pintype "bidirectional"))
    )
    (net (code "35") (name "Net-(GND-UVCC)") (class "Default")
      (node (ref "GND") (pin "2") (pinfunction "UVCC_2") (pintype "bidirectional"))
      (node (ref "U$3") (pin "2") (pinfunction "UVCC_2") (pintype "bidirectional"))
    )
    (net (code "36") (name "Net-(IC3-Q)") (class "Default")
      (node (ref "IC3") (pin "5") (pinfunction "Q_5") (pintype "output"))
      (node (ref "R21") (pin "1") (pinfunction "1_1") (pintype "passive"))
    )
    (net (code "37") (name "Net-(IC3-~{CLR})") (class "Default")
      (node (ref "IC3") (pin "6") (pinfunction "~{CLR}_6") (pintype "input"))
      (node (ref "Q4") (pin "3") (pinfunction "D_3") (pintype "passive"))
      (node (ref "R7") (pin "2") (pinfunction "2_2") (pintype "passive"))
    )
    (net (code "38") (name "Net-(IC3-~{SET})") (class "Default")
      (node (ref "IC3") (pin "7") (pinfunction "~{SET}_7") (pintype "input"))
      (node (ref "Q5") (pin "1") (pinfunction "G_1") (pintype "passive"))
      (node (ref "R6") (pin "2") (pinfunction "2_2") (pintype "passive"))
      (node (ref "S6") (pin "1") (pinfunction "1_1") (pintype "passive"))
    )
    (net (code "39") (name "Net-(Q1-G)") (class "Default")
      (node (ref "Q1") (pin "1") (pinfunction "G_1") (pintype "passive"))
      (node (ref "U2") (pin "2") (pinfunction "~{RST}_2") (pintype "bidirectional"))
    )
    (net (code "40") (name "Net-(Q2-D)") (class "Default")
      (node (ref "Q2") (pin "3") (pinfunction "D_3") (pintype "passive"))
      (node (ref "R20") (pin "2") (pinfunction "2_2") (pintype "passive"))
    )
    (net (code "41") (name "Net-(Q2-G)") (class "Default")
      (node (ref "Q2") (pin "1") (pinfunction "G_1") (pintype "passive"))
      (node (ref "Q3") (pin "3") (pinfunction "D_3") (pintype "passive"))
      (node (ref "R5") (pin "2") (pinfunction "2_2") (pintype "passive"))
    )
    (net (code "42") (name "Net-(U$1-D+)") (class "Default")
      (node (ref "R9") (pin "1") (pinfunction "1_1") (pintype "passive"))
      (node (ref "U$1") (pin "PIN$3") (pinfunction "D+_PIN$3") (pintype "bidirectional"))
      (node (ref "Z1") (pin "2") (pinfunction "2_2") (pintype "passive"))
    )
    (net (code "43") (name "Net-(U$1-D-)") (class "Default")
      (node (ref "R10") (pin "1") (pinfunction "1_1") (pintype "passive"))
      (node (ref "U$1") (pin "PIN$2") (pinfunction "D-_PIN$2") (pintype "bidirectional"))
      (node (ref "Z2") (pin "2") (pinfunction "2_2") (pintype "passive"))
    )
    (net (code "44") (name "Net-(U$2-VBAT)") (class "Default")
      (node (ref "SJ1") (pin "2") (pinfunction "2_2") (pintype "passive"))
      (node (ref "U$2") (pin "P$1") (pinfunction "VBAT_P$1") (pintype "bidirectional"))
    )
    (net (code "45") (name "Net-(U3-PROG)") (class "Default")
      (node (ref "R3") (pin "1") (pinfunction "1_1") (pintype "passive"))
      (node (ref "U3") (pin "5") (pinfunction "PROG_5") (pintype "input"))
    )
    (net (code "46") (name "Net-(U3-STAT)") (class "Default")
      (node (ref "R17") (pin "2") (pinfunction "2_2") (pintype "passive"))
      (node (ref "U3") (pin "1") (pinfunction "STAT_1") (pintype "output"))
    )
    (net (code "47") (name "Net-(U4-BP)") (class "Default")
      (node (ref "C4") (pin "1") (pinfunction "1_1") (pintype "passive"))
      (node (ref "U4") (pin "4") (pinfunction "BP_4") (pintype "input"))
    )
    (net (code "48") (name "Net-(X1C-1)") (class "Default")
      (node (ref "R19") (pin "1") (pinfunction "1_1") (pintype "passive"))
      (node (ref "X1") (pin "11") (pinfunction "1_11") (pintype "passive"))
    )
    (net (code "49") (name "Net-(X1E-1)") (class "Default")
      (node (ref "C35") (pin "2") (pinfunction "2_2") (pintype "passive"))
      (node (ref "X1") (pin "2") (pinfunction "1_2") (pintype "passive"))
    )
    (net (code "50") (name "Net-(X1F-1)") (class "Default")
      (node (ref "C35") (pin "1") (pinfunction "1_1") (pintype "passive"))
      (node (ref "X1") (pin "3") (pinfunction "1_3") (pintype "passive"))
    )
    (net (code "51") (name "SW_A") (class "Default")
      (node (ref "GND") (pin "1") (pinfunction "PE6_1") (pintype "bidirectional"))
      (node (ref "R8") (pin "2") (pinfunction "2_2") (pintype "passive"))
      (node (ref "S3") (pin "3") (pinfunction "2_3") (pintype "passive"))
      (node (ref "U$3") (pin "1") (pinfunction "PE6_1") (pintype "bidirectional"))
    )
    (net (code "52") (name "SW_B") (class "Default")
      (node (ref "GND") (pin "21") (pinfunction "PD3(TX)_21") (pintype "bidirectional"))
      (node (ref "R11") (pin "2") (pinfunction "2_2") (pintype "passive"))
      (node (ref "S2") (pin "3") (pinfunction "2_3") (pintype "passive"))
      (node (ref "U$3") (pin "21") (pinfunction "PD3(TX)_21") (pintype "bidirectional"))
    )
    (net (code "53") (name "SW_C") (class "Default")
      (node (ref "GND") (pin "28") (pinfunction "PB4(ADC11)_28") (pintype "bidirectional"))
      (node (ref "R12") (pin "2") (pinfunction "2_2") (pintype "passive"))
      (node (ref "S1") (pin "3") (pinfunction "2_3") (pintype "passive"))
      (node (ref "U$3") (pin "28") (pinfunction "PB4(ADC11)_28") (pintype "bidirectional"))
    )
    (net (code "54") (name "SW_D") (class "Default")
      (node (ref "GND") (pin "29") (pinfunction "PB5(ADC12)_29") (pintype "bidirectional"))
      (node (ref "R15") (pin "2") (pinfunction "2_2") (pintype "passive"))
      (node (ref "S4") (pin "3") (pinfunction "2_3") (pintype "passive"))
      (node (ref "U$3") (pin "29") (pinfunction "PB5(ADC12)_29") (pintype "bidirectional"))
    )
    (net (code "55") (name "SW_E") (class "Default")
      (node (ref "GND") (pin "30") (pinfunction "PB6(ADC13)_30") (pintype "bidirectional"))
      (node (ref "R16") (pin "2") (pinfunction "2_2") (pintype "passive"))
      (node (ref "S5") (pin "3") (pinfunction "2_3") (pintype "passive"))
      (node (ref "U$3") (pin "30") (pinfunction "PB6(ADC13)_30") (pintype "bidirectional"))
    )
    (net (code "56") (name "unconnected-(IC3-~{Q}-Pad3)") (class "Default")
      (node (ref "IC3") (pin "3") (pinfunction "~{Q}_3") (pintype "output"))
    )
    (net (code "57") (name "unconnected-(ICSP1-Pad3)") (class "Default")
      (node (ref "ICSP1") (pin "3") (pinfunction "3_3") (pintype "bidirectional"))
    )
    (net (code "58") (name "unconnected-(ICSP1-Pad4)") (class "Default")
      (node (ref "ICSP1") (pin "4") (pinfunction "4_4") (pintype "bidirectional"))
    )
    (net (code "59") (name "unconnected-(J1-CDN-Pad9)") (class "Default")
      (node (ref "J1") (pin "9") (pinfunction "CDN_9") (pintype "bidirectional"))
    )
    (net (code "60") (name "unconnected-(J1-DATA1-Pad8)") (class "Default")
      (node (ref "J1") (pin "8") (pinfunction "DATA1_8") (pintype "bidirectional"))
    )
    (net (code "61") (name "unconnected-(J1-DATA2-Pad1)") (class "Default")
      (node (ref "J1") (pin "1") (pinfunction "DATA2_1") (pintype "bidirectional"))
    )
    (net (code "62") (name "unconnected-(U$1-ID-PadPIN$4)") (class "Default")
      (node (ref "U$1") (pin "PIN$4") (pinfunction "ID_PIN$4") (pintype "bidirectional"))
    )
    (net (code "63") (name "unconnected-(U$2-BSI-PadP$2)") (class "Default")
      (node (ref "U$2") (pin "P$2") (pinfunction "BSI_P$2") (pintype "bidirectional"))
    )
    (net (code "64") (name "unconnected-(U$7-INT-PadP$8)") (class "Default")
      (node (ref "U$7") (pin "P$8") (pinfunction "INT_P$8") (pintype "output"))
    )
    (net (code "65") (name "unconnected-(U$14-32KHZ-Pad1)") (class "Default")
      (node (ref "U$14") (pin "1") (pinfunction "32KHZ_1") (pintype "output"))
    )
    (net (code "66") (name "unconnected-(U$14-RST-Pad4)") (class "Default")
      (node (ref "U$14") (pin "4") (pinfunction "RST_4") (pintype "bidirectional"))
    )
  )
)
